# TC4Server_Test.net
KiCad netlist of a schematic drawn in EAGLE
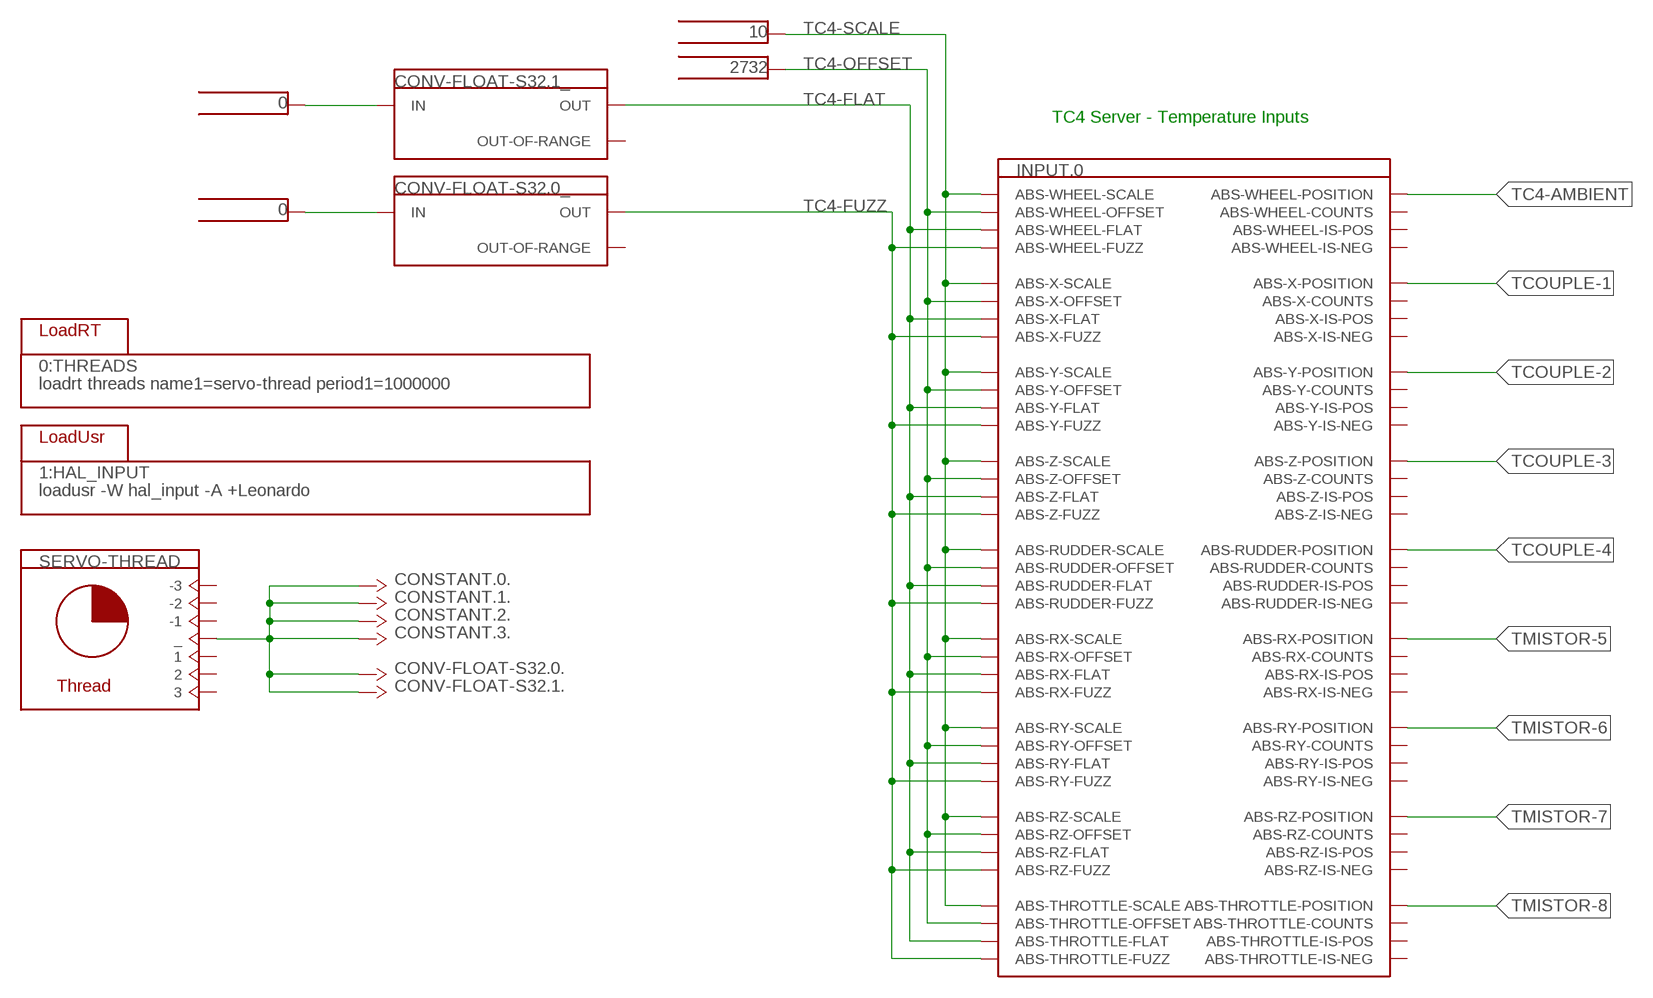
[diagram p0: schematic, sheet 1]

(export (version "E")
  (design (tool "Eeschema 10.0.6"))
  (components
    (comp (ref "0:THREADS")
      (value "loadrt threads name1=servo-thread period1=1000000")
      (footprint "eagle-import:DUMMY")
      (libsource (lib "eagle-import") (part "LOADRT"))
    )
    (comp (ref "CONSTANT.0")
      (value "10")
      (footprint "eagle-import:DUMMY")
      (libsource (lib "eagle-import") (part "CONSTANT"))
    )
    (comp (ref "CONSTANT.1")
      (value "2732")
      (footprint "eagle-import:DUMMY")
      (libsource (lib "eagle-import") (part "CONSTANT"))
    )
    (comp (ref "CONSTANT.2")
      (value "0")
      (footprint "eagle-import:DUMMY")
      (libsource (lib "eagle-import") (part "CONSTANT"))
    )
    (comp (ref "CONSTANT.3")
      (value "0")
      (footprint "eagle-import:DUMMY")
      (libsource (lib "eagle-import") (part "CONSTANT"))
    )
    (comp (ref "CONV-FLOAT-S32.0")
      (value "CONV_FLOAT_S32")
      (footprint "eagle-import:DUMMY")
      (libsource (lib "eagle-import") (part "CONV_FLOAT_S32"))
    )
    (comp (ref "CONV-FLOAT-S32.1")
      (value "CONV_FLOAT_S32")
      (footprint "eagle-import:DUMMY")
      (libsource (lib "eagle-import") (part "CONV_FLOAT_S32"))
    )
    (comp (ref "INPUT.0")
      (value "JOYSTICK")
      (footprint "eagle-import:DUMMY")
      (libsource (lib "eagle-import") (part "JOYSTICK"))
    )
    (comp (ref "SERVO-THREAD")
      (value "THREAD")
      (footprint "eagle-import:DUMMY")
      (libsource (lib "eagle-import") (part "THREAD"))
    )
  )
  (nets
    (net (code "1") (name "/TC4-FLAT") (class "Default")
      (node (ref "CONV-FLOAT-S32.1") (pin "P$4") (pinfunction "OUT_P$4") (pintype "output"))
      (node (ref "INPUT.0") (pin "P$10") (pinfunction "ABS-RX-FLAT_P$10") (pintype "input"))
      (node (ref "INPUT.0") (pin "P$18") (pinfunction "ABS-RY-FLAT_P$18") (pintype "input"))
      (node (ref "INPUT.0") (pin "P$2") (pinfunction "ABS-RUDDER-FLAT_P$2") (pintype "input"))
      (node (ref "INPUT.0") (pin "P$26") (pinfunction "ABS-RZ-FLAT_P$26") (pintype "input"))
      (node (ref "INPUT.0") (pin "P$34") (pinfunction "ABS-THROTTLE-FLAT_P$34") (pintype "input"))
      (node (ref "INPUT.0") (pin "P$42") (pinfunction "ABS-WHEEL-FLAT_P$42") (pintype "input"))
      (node (ref "INPUT.0") (pin "P$50") (pinfunction "ABS-X-FLAT_P$50") (pintype "input"))
      (node (ref "INPUT.0") (pin "P$58") (pinfunction "ABS-Y-FLAT_P$58") (pintype "input"))
      (node (ref "INPUT.0") (pin "P$66") (pinfunction "ABS-Z-FLAT_P$66") (pintype "input"))
    )
    (net (code "2") (name "/TC4-FUZZ") (class "Default")
      (node (ref "CONV-FLOAT-S32.0") (pin "P$4") (pinfunction "OUT_P$4") (pintype "output"))
      (node (ref "INPUT.0") (pin "P$11") (pinfunction "ABS-RX-FUZZ_P$11") (pintype "input"))
      (node (ref "INPUT.0") (pin "P$19") (pinfunction "ABS-RY-FUZZ_P$19") (pintype "input"))
      (node (ref "INPUT.0") (pin "P$27") (pinfunction "ABS-RZ-FUZZ_P$27") (pintype "input"))
      (node (ref "INPUT.0") (pin "P$3") (pinfunction "ABS-RUDDER-FUZZ_P$3") (pintype "input"))
      (node (ref "INPUT.0") (pin "P$35") (pinfunction "ABS-THROTTLE-FUZZ_P$35") (pintype "input"))
      (node (ref "INPUT.0") (pin "P$43") (pinfunction "ABS-WHEEL-FUZZ_P$43") (pintype "input"))
      (node (ref "INPUT.0") (pin "P$51") (pinfunction "ABS-X-FUZZ_P$51") (pintype "input"))
      (node (ref "INPUT.0") (pin "P$59") (pinfunction "ABS-Y-FUZZ_P$59") (pintype "input"))
      (node (ref "INPUT.0") (pin "P$67") (pinfunction "ABS-Z-FUZZ_P$67") (pintype "input"))
    )
    (net (code "3") (name "/TC4-OFFSET") (class "Default")
      (node (ref "CONSTANT.1") (pin "P$2") (pinfunction "OUT_P$2") (pintype "output"))
      (node (ref "INPUT.0") (pin "P$14") (pinfunction "ABS-RX-OFFSET_P$14") (pintype "input"))
      (node (ref "INPUT.0") (pin "P$22") (pinfunction "ABS-RY-OFFSET_P$22") (pintype "input"))
      (node (ref "INPUT.0") (pin "P$30") (pinfunction "ABS-RZ-OFFSET_P$30") (pintype "input"))
      (node (ref "INPUT.0") (pin "P$38") (pinfunction "ABS-THROTTLE-OFFSET_P$38") (pintype "input"))
      (node (ref "INPUT.0") (pin "P$46") (pinfunction "ABS-WHEEL-OFFSET_P$46") (pintype "input"))
      (node (ref "INPUT.0") (pin "P$54") (pinfunction "ABS-X-OFFSET_P$54") (pintype "input"))
      (node (ref "INPUT.0") (pin "P$6") (pinfunction "ABS-RUDDER-OFFSET_P$6") (pintype "input"))
      (node (ref "INPUT.0") (pin "P$62") (pinfunction "ABS-Y-OFFSET_P$62") (pintype "input"))
      (node (ref "INPUT.0") (pin "P$70") (pinfunction "ABS-Z-OFFSET_P$70") (pintype "input"))
    )
    (net (code "4") (name "/TC4-SCALE") (class "Default")
      (node (ref "CONSTANT.0") (pin "P$2") (pinfunction "OUT_P$2") (pintype "output"))
      (node (ref "INPUT.0") (pin "P$16") (pinfunction "ABS-RX-SCALE_P$16") (pintype "input"))
      (node (ref "INPUT.0") (pin "P$24") (pinfunction "ABS-RY-SCALE_P$24") (pintype "input"))
      (node (ref "INPUT.0") (pin "P$32") (pinfunction "ABS-RZ-SCALE_P$32") (pintype "input"))
      (node (ref "INPUT.0") (pin "P$40") (pinfunction "ABS-THROTTLE-SCALE_P$40") (pintype "input"))
      (node (ref "INPUT.0") (pin "P$48") (pinfunction "ABS-WHEEL-SCALE_P$48") (pintype "input"))
      (node (ref "INPUT.0") (pin "P$56") (pinfunction "ABS-X-SCALE_P$56") (pintype "input"))
      (node (ref "INPUT.0") (pin "P$64") (pinfunction "ABS-Y-SCALE_P$64") (pintype "input"))
      (node (ref "INPUT.0") (pin "P$72") (pinfunction "ABS-Z-SCALE_P$72") (pintype "input"))
      (node (ref "INPUT.0") (pin "P$8") (pinfunction "ABS-RUDDER-SCALE_P$8") (pintype "input"))
    )
    (net (code "5") (name "Net-(CONSTANT.0A-PIN_THREAD)") (class "Default")
      (node (ref "CONSTANT.0") (pin "P$1") (pinfunction "PIN_THREAD_P$1") (pintype "bidirectional"))
      (node (ref "CONSTANT.1") (pin "P$1") (pinfunction "PIN_THREAD_P$1") (pintype "bidirectional"))
      (node (ref "CONSTANT.2") (pin "P$1") (pinfunction "PIN_THREAD_P$1") (pintype "bidirectional"))
      (node (ref "CONSTANT.3") (pin "P$1") (pinfunction "PIN_THREAD_P$1") (pintype "bidirectional"))
      (node (ref "CONV-FLOAT-S32.0") (pin "P$1") (pinfunction "PIN_THREAD_P$1") (pintype "bidirectional"))
      (node (ref "CONV-FLOAT-S32.1") (pin "P$1") (pinfunction "PIN_THREAD_P$1") (pintype "bidirectional"))
      (node (ref "SERVO-THREAD") (pin "P$7") (pinfunction "__P$7") (pintype "output"))
    )
    (net (code "6") (name "Net-(CONSTANT.2B-OUT)") (class "Default")
      (node (ref "CONSTANT.2") (pin "P$2") (pinfunction "OUT_P$2") (pintype "output"))
      (node (ref "CONV-FLOAT-S32.1") (pin "P$3") (pinfunction "IN_P$3") (pintype "input"))
    )
    (net (code "7") (name "Net-(CONSTANT.3B-OUT)") (class "Default")
      (node (ref "CONSTANT.3") (pin "P$2") (pinfunction "OUT_P$2") (pintype "output"))
      (node (ref "CONV-FLOAT-S32.0") (pin "P$3") (pinfunction "IN_P$3") (pintype "input"))
    )
    (net (code "8") (name "TC4-AMBIENT") (class "Default")
      (node (ref "INPUT.0") (pin "P$47") (pinfunction "ABS-WHEEL-POSITION_P$47") (pintype "output"))
    )
    (net (code "9") (name "TCOUPLE-1") (class "Default")
      (node (ref "INPUT.0") (pin "P$55") (pinfunction "ABS-X-POSITION_P$55") (pintype "output"))
    )
    (net (code "10") (name "TCOUPLE-2") (class "Default")
      (node (ref "INPUT.0") (pin "P$63") (pinfunction "ABS-Y-POSITION_P$63") (pintype "output"))
    )
    (net (code "11") (name "TCOUPLE-3") (class "Default")
      (node (ref "INPUT.0") (pin "P$71") (pinfunction "ABS-Z-POSITION_P$71") (pintype "output"))
    )
    (net (code "12") (name "TCOUPLE-4") (class "Default")
      (node (ref "INPUT.0") (pin "P$7") (pinfunction "ABS-RUDDER-POSITION_P$7") (pintype "output"))
    )
    (net (code "13") (name "TMISTOR-5") (class "Default")
      (node (ref "INPUT.0") (pin "P$15") (pinfunction "ABS-RX-POSITION_P$15") (pintype "output"))
    )
    (net (code "14") (name "TMISTOR-6") (class "Default")
      (node (ref "INPUT.0") (pin "P$23") (pinfunction "ABS-RY-POSITION_P$23") (pintype "output"))
    )
    (net (code "15") (name "TMISTOR-7") (class "Default")
      (node (ref "INPUT.0") (pin "P$31") (pinfunction "ABS-RZ-POSITION_P$31") (pintype "output"))
    )
    (net (code "16") (name "TMISTOR-8") (class "Default")
      (node (ref "INPUT.0") (pin "P$39") (pinfunction "ABS-THROTTLE-POSITION_P$39") (pintype "output"))
    )
    (net (code "17") (name "unconnected-(CONV-FLOAT-S32.0C-OUT-OF-RANGE-PadP$5)") (class "Default")
      (node (ref "CONV-FLOAT-S32.0") (pin "P$5") (pinfunction "OUT-OF-RANGE_P$5") (pintype "output"))
    )
    (net (code "18") (name "unconnected-(CONV-FLOAT-S32.1C-OUT-OF-RANGE-PadP$5)") (class "Default")
      (node (ref "CONV-FLOAT-S32.1") (pin "P$5") (pinfunction "OUT-OF-RANGE_P$5") (pintype "output"))
    )
    (net (code "19") (name "unconnected-(INPUT.0-ABS-RUDDER-COUNTS-PadP$1)") (class "Default")
      (node (ref "INPUT.0") (pin "P$1") (pinfunction "ABS-RUDDER-COUNTS_P$1") (pintype "output"))
    )
    (net (code "20") (name "unconnected-(INPUT.0-ABS-RUDDER-IS-NEG-PadP$4)") (class "Default")
      (node (ref "INPUT.0") (pin "P$4") (pinfunction "ABS-RUDDER-IS-NEG_P$4") (pintype "output"))
    )
    (net (code "21") (name "unconnected-(INPUT.0-ABS-RUDDER-IS-POS-PadP$5)") (class "Default")
      (node (ref "INPUT.0") (pin "P$5") (pinfunction "ABS-RUDDER-IS-POS_P$5") (pintype "output"))
    )
    (net (code "22") (name "unconnected-(INPUT.0-ABS-RX-COUNTS-PadP$9)") (class "Default")
      (node (ref "INPUT.0") (pin "P$9") (pinfunction "ABS-RX-COUNTS_P$9") (pintype "output"))
    )
    (net (code "23") (name "unconnected-(INPUT.0-ABS-RX-IS-NEG-PadP$12)") (class "Default")
      (node (ref "INPUT.0") (pin "P$12") (pinfunction "ABS-RX-IS-NEG_P$12") (pintype "output"))
    )
    (net (code "24") (name "unconnected-(INPUT.0-ABS-RX-IS-POS-PadP$13)") (class "Default")
      (node (ref "INPUT.0") (pin "P$13") (pinfunction "ABS-RX-IS-POS_P$13") (pintype "output"))
    )
    (net (code "25") (name "unconnected-(INPUT.0-ABS-RY-COUNTS-PadP$17)") (class "Default")
      (node (ref "INPUT.0") (pin "P$17") (pinfunction "ABS-RY-COUNTS_P$17") (pintype "output"))
    )
    (net (code "26") (name "unconnected-(INPUT.0-ABS-RY-IS-NEG-PadP$20)") (class "Default")
      (node (ref "INPUT.0") (pin "P$20") (pinfunction "ABS-RY-IS-NEG_P$20") (pintype "output"))
    )
    (net (code "27") (name "unconnected-(INPUT.0-ABS-RY-IS-POS-PadP$21)") (class "Default")
      (node (ref "INPUT.0") (pin "P$21") (pinfunction "ABS-RY-IS-POS_P$21") (pintype "output"))
    )
    (net (code "28") (name "unconnected-(INPUT.0-ABS-RZ-COUNTS-PadP$25)") (class "Default")
      (node (ref "INPUT.0") (pin "P$25") (pinfunction "ABS-RZ-COUNTS_P$25") (pintype "output"))
    )
    (net (code "29") (name "unconnected-(INPUT.0-ABS-RZ-IS-NEG-PadP$28)") (class "Default")
      (node (ref "INPUT.0") (pin "P$28") (pinfunction "ABS-RZ-IS-NEG_P$28") (pintype "output"))
    )
    (net (code "30") (name "unconnected-(INPUT.0-ABS-RZ-IS-POS-PadP$29)") (class "Default")
      (node (ref "INPUT.0") (pin "P$29") (pinfunction "ABS-RZ-IS-POS_P$29") (pintype "output"))
    )
    (net (code "31") (name "unconnected-(INPUT.0-ABS-THROTTLE-COUNTS-PadP$33)") (class "Default")
      (node (ref "INPUT.0") (pin "P$33") (pinfunction "ABS-THROTTLE-COUNTS_P$33") (pintype "output"))
    )
    (net (code "32") (name "unconnected-(INPUT.0-ABS-THROTTLE-IS-NEG-PadP$36)") (class "Default")
      (node (ref "INPUT.0") (pin "P$36") (pinfunction "ABS-THROTTLE-IS-NEG_P$36") (pintype "output"))
    )
    (net (code "33") (name "unconnected-(INPUT.0-ABS-THROTTLE-IS-POS-PadP$37)") (class "Default")
      (node (ref "INPUT.0") (pin "P$37") (pinfunction "ABS-THROTTLE-IS-POS_P$37") (pintype "output"))
    )
    (net (code "34") (name "unconnected-(INPUT.0-ABS-WHEEL-COUNTS-PadP$41)") (class "Default")
      (node (ref "INPUT.0") (pin "P$41") (pinfunction "ABS-WHEEL-COUNTS_P$41") (pintype "output"))
    )
    (net (code "35") (name "unconnected-(INPUT.0-ABS-WHEEL-IS-NEG-PadP$44)") (class "Default")
      (node (ref "INPUT.0") (pin "P$44") (pinfunction "ABS-WHEEL-IS-NEG_P$44") (pintype "output"))
    )
    (net (code "36") (name "unconnected-(INPUT.0-ABS-WHEEL-IS-POS-PadP$45)") (class "Default")
      (node (ref "INPUT.0") (pin "P$45") (pinfunction "ABS-WHEEL-IS-POS_P$45") (pintype "output"))
    )
    (net (code "37") (name "unconnected-(INPUT.0-ABS-X-COUNTS-PadP$49)") (class "Default")
      (node (ref "INPUT.0") (pin "P$49") (pinfunction "ABS-X-COUNTS_P$49") (pintype "output"))
    )
    (net (code "38") (name "unconnected-(INPUT.0-ABS-X-IS-NEG-PadP$52)") (class "Default")
      (node (ref "INPUT.0") (pin "P$52") (pinfunction "ABS-X-IS-NEG_P$52") (pintype "output"))
    )
    (net (code "39") (name "unconnected-(INPUT.0-ABS-X-IS-POS-PadP$53)") (class "Default")
      (node (ref "INPUT.0") (pin "P$53") (pinfunction "ABS-X-IS-POS_P$53") (pintype "output"))
    )
    (net (code "40") (name "unconnected-(INPUT.0-ABS-Y-COUNTS-PadP$57)") (class "Default")
      (node (ref "INPUT.0") (pin "P$57") (pinfunction "ABS-Y-COUNTS_P$57") (pintype "output"))
    )
    (net (code "41") (name "unconnected-(INPUT.0-ABS-Y-IS-NEG-PadP$60)") (class "Default")
      (node (ref "INPUT.0") (pin "P$60") (pinfunction "ABS-Y-IS-NEG_P$60") (pintype "output"))
    )
    (net (code "42") (name "unconnected-(INPUT.0-ABS-Y-IS-POS-PadP$61)") (class "Default")
      (node (ref "INPUT.0") (pin "P$61") (pinfunction "ABS-Y-IS-POS_P$61") (pintype "output"))
    )
    (net (code "43") (name "unconnected-(INPUT.0-ABS-Z-COUNTS-PadP$65)") (class "Default")
      (node (ref "INPUT.0") (pin "P$65") (pinfunction "ABS-Z-COUNTS_P$65") (pintype "output"))
    )
    (net (code "44") (name "unconnected-(INPUT.0-ABS-Z-IS-NEG-PadP$68)") (class "Default")
      (node (ref "INPUT.0") (pin "P$68") (pinfunction "ABS-Z-IS-NEG_P$68") (pintype "output"))
    )
    (net (code "45") (name "unconnected-(INPUT.0-ABS-Z-IS-POS-PadP$69)") (class "Default")
      (node (ref "INPUT.0") (pin "P$69") (pinfunction "ABS-Z-IS-POS_P$69") (pintype "output"))
    )
    (net (code "46") (name "unconnected-(SERVO-THREAD--1-PadP$1)") (class "Default")
      (node (ref "SERVO-THREAD") (pin "P$1") (pinfunction "-1_P$1") (pintype "output"))
    )
    (net (code "47") (name "unconnected-(SERVO-THREAD--2-PadP$2)") (class "Default")
      (node (ref "SERVO-THREAD") (pin "P$2") (pinfunction "-2_P$2") (pintype "output"))
    )
    (net (code "48") (name "unconnected-(SERVO-THREAD--3-PadP$3)") (class "Default")
      (node (ref "SERVO-THREAD") (pin "P$3") (pinfunction "-3_P$3") (pintype "output"))
    )
    (net (code "49") (name "unconnected-(SERVO-THREAD-1-PadP$4)") (class "Default")
      (node (ref "SERVO-THREAD") (pin "P$4") (pinfunction "1_P$4") (pintype "output"))
    )
    (net (code "50") (name "unconnected-(SERVO-THREAD-2-PadP$5)") (class "Default")
      (node (ref "SERVO-THREAD") (pin "P$5") (pinfunction "2_P$5") (pintype "output"))
    )
    (net (code "51") (name "unconnected-(SERVO-THREAD-3-PadP$6)") (class "Default")
      (node (ref "SERVO-THREAD") (pin "P$6") (pinfunction "3_P$6") (pintype "output"))
    )
  )
)
